# TDC_CH.net
KiCad netlist of a schematic drawn in Altium Designer
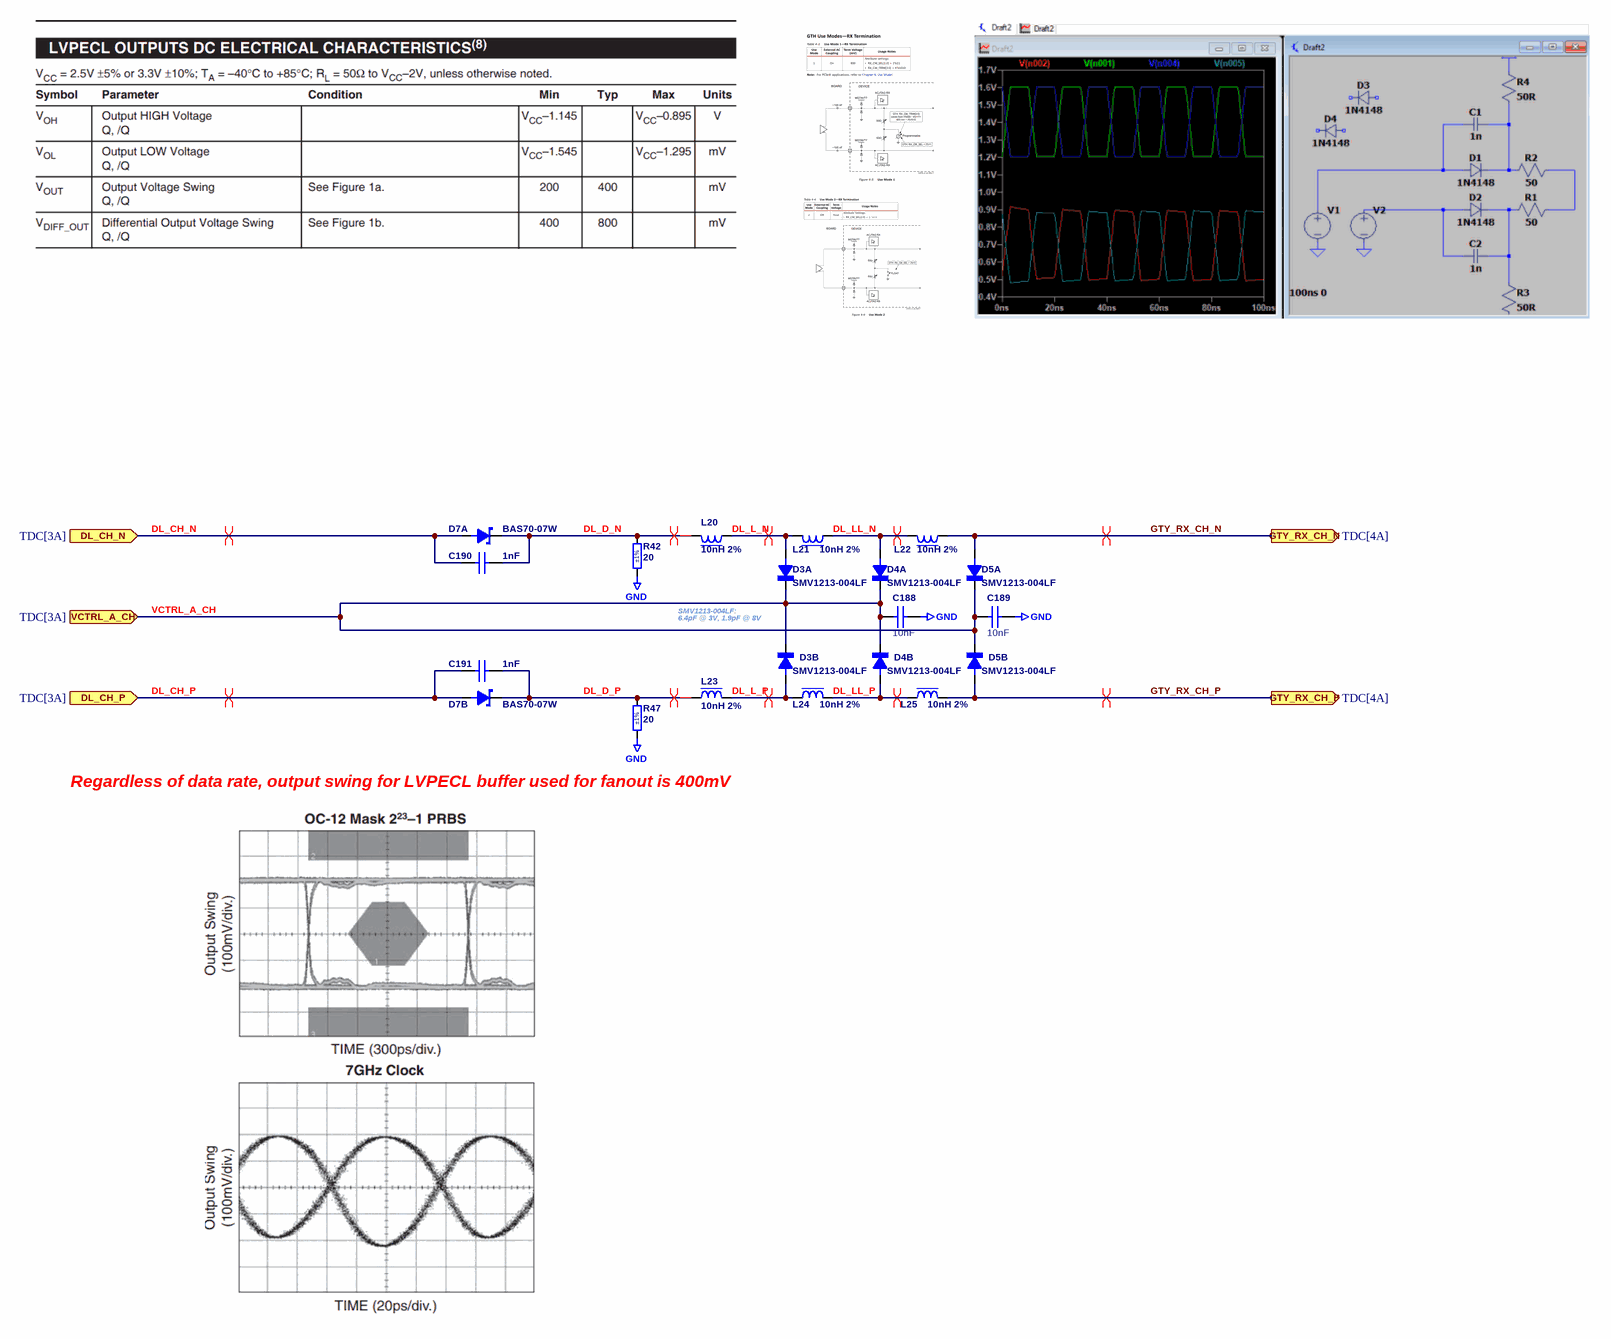
[diagram p0: TDC_CH.SchDoc]

(export (version "E")
  (design (tool "Eeschema 10.0.6"))
  (components
    (comp (ref "C188")
      (value "10nF")
      (footprint "CAPC1005X55N")
      (description "Non-polarised capacitor")
      (fields
        (field (name "PART NUMBER") "CC0402_10NF_50V_10%_X7R")
        (field (name "VOLTAGE") "50V")
        (field (name "AUTHOR") "CERN DEM MR")
      )
      (libsource (lib "Capacitors") (part "Capacitor - non polarized"))
    )
    (comp (ref "C189")
      (value "10nF")
      (footprint "CAPC1005X55N")
      (description "Non-polarised capacitor")
      (fields
        (field (name "PART NUMBER") "CC0402_10NF_50V_10%_X7R")
        (field (name "VOLTAGE") "50V")
        (field (name "AUTHOR") "CERN DEM MR")
      )
      (libsource (lib "Capacitors") (part "Capacitor - non polarized"))
    )
    (comp (ref "C190")
      (value "1nF")
      (footprint "CAPC1005X55N")
      (description "Non-polarised capacitor")
      (fields
        (field (name "PART NUMBER") "CC0402_1NF_50V_10%_X7R")
        (field (name "VOLTAGE") "50V")
        (field (name "AUTHOR") "CERN DEM JLC")
      )
      (libsource (lib "Capacitors") (part "Capacitor - non polarized"))
    )
    (comp (ref "C191")
      (value "1nF")
      (footprint "CAPC1005X55N")
      (description "Non-polarised capacitor")
      (fields
        (field (name "PART NUMBER") "CC0402_1NF_50V_10%_X7R")
        (field (name "VOLTAGE") "50V")
        (field (name "AUTHOR") "CERN DEM JLC")
      )
      (libsource (lib "Capacitors") (part "Capacitor - non polarized"))
    )
    (comp (ref "D3")
      (value "SMV1213-004LF")
      (footprint "SOT23")
      (description "Hyperabrupt Junction Tuning Varactors , double, common cathode")
      (libsource (lib "MISCELANOUS") (part "DIODE_SMV1213"))
    )
    (comp (ref "D4")
      (value "SMV1213-004LF")
      (footprint "SOT23")
      (description "Hyperabrupt Junction Tuning Varactors , double, common cathode")
      (libsource (lib "") (part "DIODE_SMV1213_1"))
    )
    (comp (ref "D5")
      (value "SMV1213-004LF")
      (footprint "SOT23")
      (description "Hyperabrupt Junction Tuning Varactors , double, common cathode")
      (libsource (lib "MISCELANOUS") (part "DIODE_SMV1213"))
    )
    (comp (ref "D7")
      (value "BAS70-07W")
      (footprint "SOT135P210X100-4N")
      (description "General-purpose diode for high-speed switching")
      (libsource (lib "MISCELANOUS") (part "DIODE_BAS70-07W"))
    )
    (comp (ref "L20")
      (value "10nH 2%")
      (footprint "R0402")
      (libsource (lib "") (part "IND_LQW15AN10NG00D_1"))
    )
    (comp (ref "L21")
      (value "10nH 2%")
      (footprint "R0402")
      (libsource (lib "") (part "IND_LQW15AN10NG00D_1"))
    )
    (comp (ref "L22")
      (value "10nH 2%")
      (footprint "R0402")
      (libsource (lib "") (part "IND_LQW15AN10NG00D_1"))
    )
    (comp (ref "L23")
      (value "10nH 2%")
      (footprint "R0402")
      (libsource (lib "MISCELANOUS") (part "IND_LQW15AN10NG00D"))
    )
    (comp (ref "L24")
      (value "10nH 2%")
      (footprint "R0402")
      (libsource (lib "MISCELANOUS") (part "IND_LQW15AN10NG00D"))
    )
    (comp (ref "L25")
      (value "10nH 2%")
      (footprint "R0402")
      (libsource (lib "MISCELANOUS") (part "IND_LQW15AN10NG00D"))
    )
    (comp (ref "R42")
      (value "20")
      (footprint "RESC1005X40N")
      (description "Resistor - 1%")
      (fields
        (field (name "TOLERANCE") "±1%")
        (field (name "PART NUMBER") "R0402_20R_1%_0.0625W_100PPM")
        (field (name "POWER") "0.0625W")
        (field (name "AUTHOR") "CERN DEM JLC")
      )
      (libsource (lib "Resistors") (part "Resistor - 1%"))
    )
    (comp (ref "R47")
      (value "20")
      (footprint "RESC1005X40N")
      (description "Resistor - 1%")
      (fields
        (field (name "TOLERANCE") "±1%")
        (field (name "PART NUMBER") "R0402_20R_1%_0.0625W_100PPM")
        (field (name "POWER") "0.0625W")
        (field (name "AUTHOR") "CERN DEM JLC")
      )
      (libsource (lib "Resistors") (part "Resistor - 1%"))
    )
  )
  (nets
    (net (code "1") (name "/DL_CH_N") (class "Default")
      (node (ref "C190") (pin "1") (pinfunction "1_1") (pintype "passive"))
      (node (ref "D7") (pin "4") (pinfunction "A_4") (pintype "passive"))
    )
    (net (code "2") (name "/DL_CH_P") (class "Default")
      (node (ref "C191") (pin "1") (pinfunction "1_1") (pintype "passive"))
      (node (ref "D7") (pin "3") (pinfunction "A_3") (pintype "passive"))
    )
    (net (code "3") (name "/DL_D_N") (class "Default")
      (node (ref "C190") (pin "2") (pinfunction "2_2") (pintype "passive"))
      (node (ref "D7") (pin "1") (pinfunction "K_1") (pintype "passive"))
      (node (ref "L20") (pin "1") (pinfunction "1_1") (pintype "passive"))
      (node (ref "R42") (pin "2") (pinfunction "2_2") (pintype "passive"))
    )
    (net (code "4") (name "/DL_D_P") (class "Default")
      (node (ref "C191") (pin "2") (pinfunction "2_2") (pintype "passive"))
      (node (ref "D7") (pin "2") (pinfunction "K_2") (pintype "passive"))
      (node (ref "L23") (pin "1") (pinfunction "1_1") (pintype "passive"))
      (node (ref "R47") (pin "2") (pinfunction "2_2") (pintype "passive"))
    )
    (net (code "5") (name "/DL_LL_N") (class "Default")
      (node (ref "D4") (pin "1") (pinfunction "A_1") (pintype "passive"))
      (node (ref "L21") (pin "2") (pinfunction "2_2") (pintype "passive"))
      (node (ref "L22") (pin "1") (pinfunction "1_1") (pintype "passive"))
    )
    (net (code "6") (name "/DL_LL_P") (class "Default")
      (node (ref "D4") (pin "2") (pinfunction "A_2") (pintype "passive"))
      (node (ref "L24") (pin "2") (pinfunction "2_2") (pintype "passive"))
      (node (ref "L25") (pin "1") (pinfunction "1_1") (pintype "passive"))
    )
    (net (code "7") (name "/DL_L_N") (class "Default")
      (node (ref "D3") (pin "1") (pinfunction "A_1") (pintype "passive"))
      (node (ref "L20") (pin "2") (pinfunction "2_2") (pintype "passive"))
      (node (ref "L21") (pin "1") (pinfunction "1_1") (pintype "passive"))
    )
    (net (code "8") (name "/DL_L_P") (class "Default")
      (node (ref "D3") (pin "2") (pinfunction "A_2") (pintype "passive"))
      (node (ref "L23") (pin "2") (pinfunction "2_2") (pintype "passive"))
      (node (ref "L24") (pin "1") (pinfunction "1_1") (pintype "passive"))
    )
    (net (code "9") (name "/GTY_RX_CH_N") (class "Default")
      (node (ref "D5") (pin "1") (pinfunction "A_1") (pintype "passive"))
      (node (ref "L22") (pin "2") (pinfunction "2_2") (pintype "passive"))
    )
    (net (code "10") (name "/GTY_RX_CH_P") (class "Default")
      (node (ref "D5") (pin "2") (pinfunction "A_2") (pintype "passive"))
      (node (ref "L25") (pin "2") (pinfunction "2_2") (pintype "passive"))
    )
    (net (code "11") (name "/VCTRL_A_CH") (class "Default")
      (node (ref "C188") (pin "2") (pinfunction "2_2") (pintype "passive"))
      (node (ref "C189") (pin "2") (pinfunction "2_2") (pintype "passive"))
      (node (ref "D3") (pin "3") (pinfunction "K_3") (pintype "passive"))
      (node (ref "D4") (pin "3") (pinfunction "K_3") (pintype "passive"))
      (node (ref "D5") (pin "3") (pinfunction "K_3") (pintype "passive"))
    )
    (net (code "12") (name "GND") (class "Default")
      (node (ref "C188") (pin "1") (pinfunction "1_1") (pintype "passive"))
      (node (ref "C189") (pin "1") (pinfunction "1_1") (pintype "passive"))
      (node (ref "R42") (pin "1") (pinfunction "1_1") (pintype "passive"))
      (node (ref "R47") (pin "1") (pinfunction "1_1") (pintype "passive"))
    )
  )
)
